# QS40_pcb_1_6_2.net
KiCad netlist of a schematic drawn in EAGLE
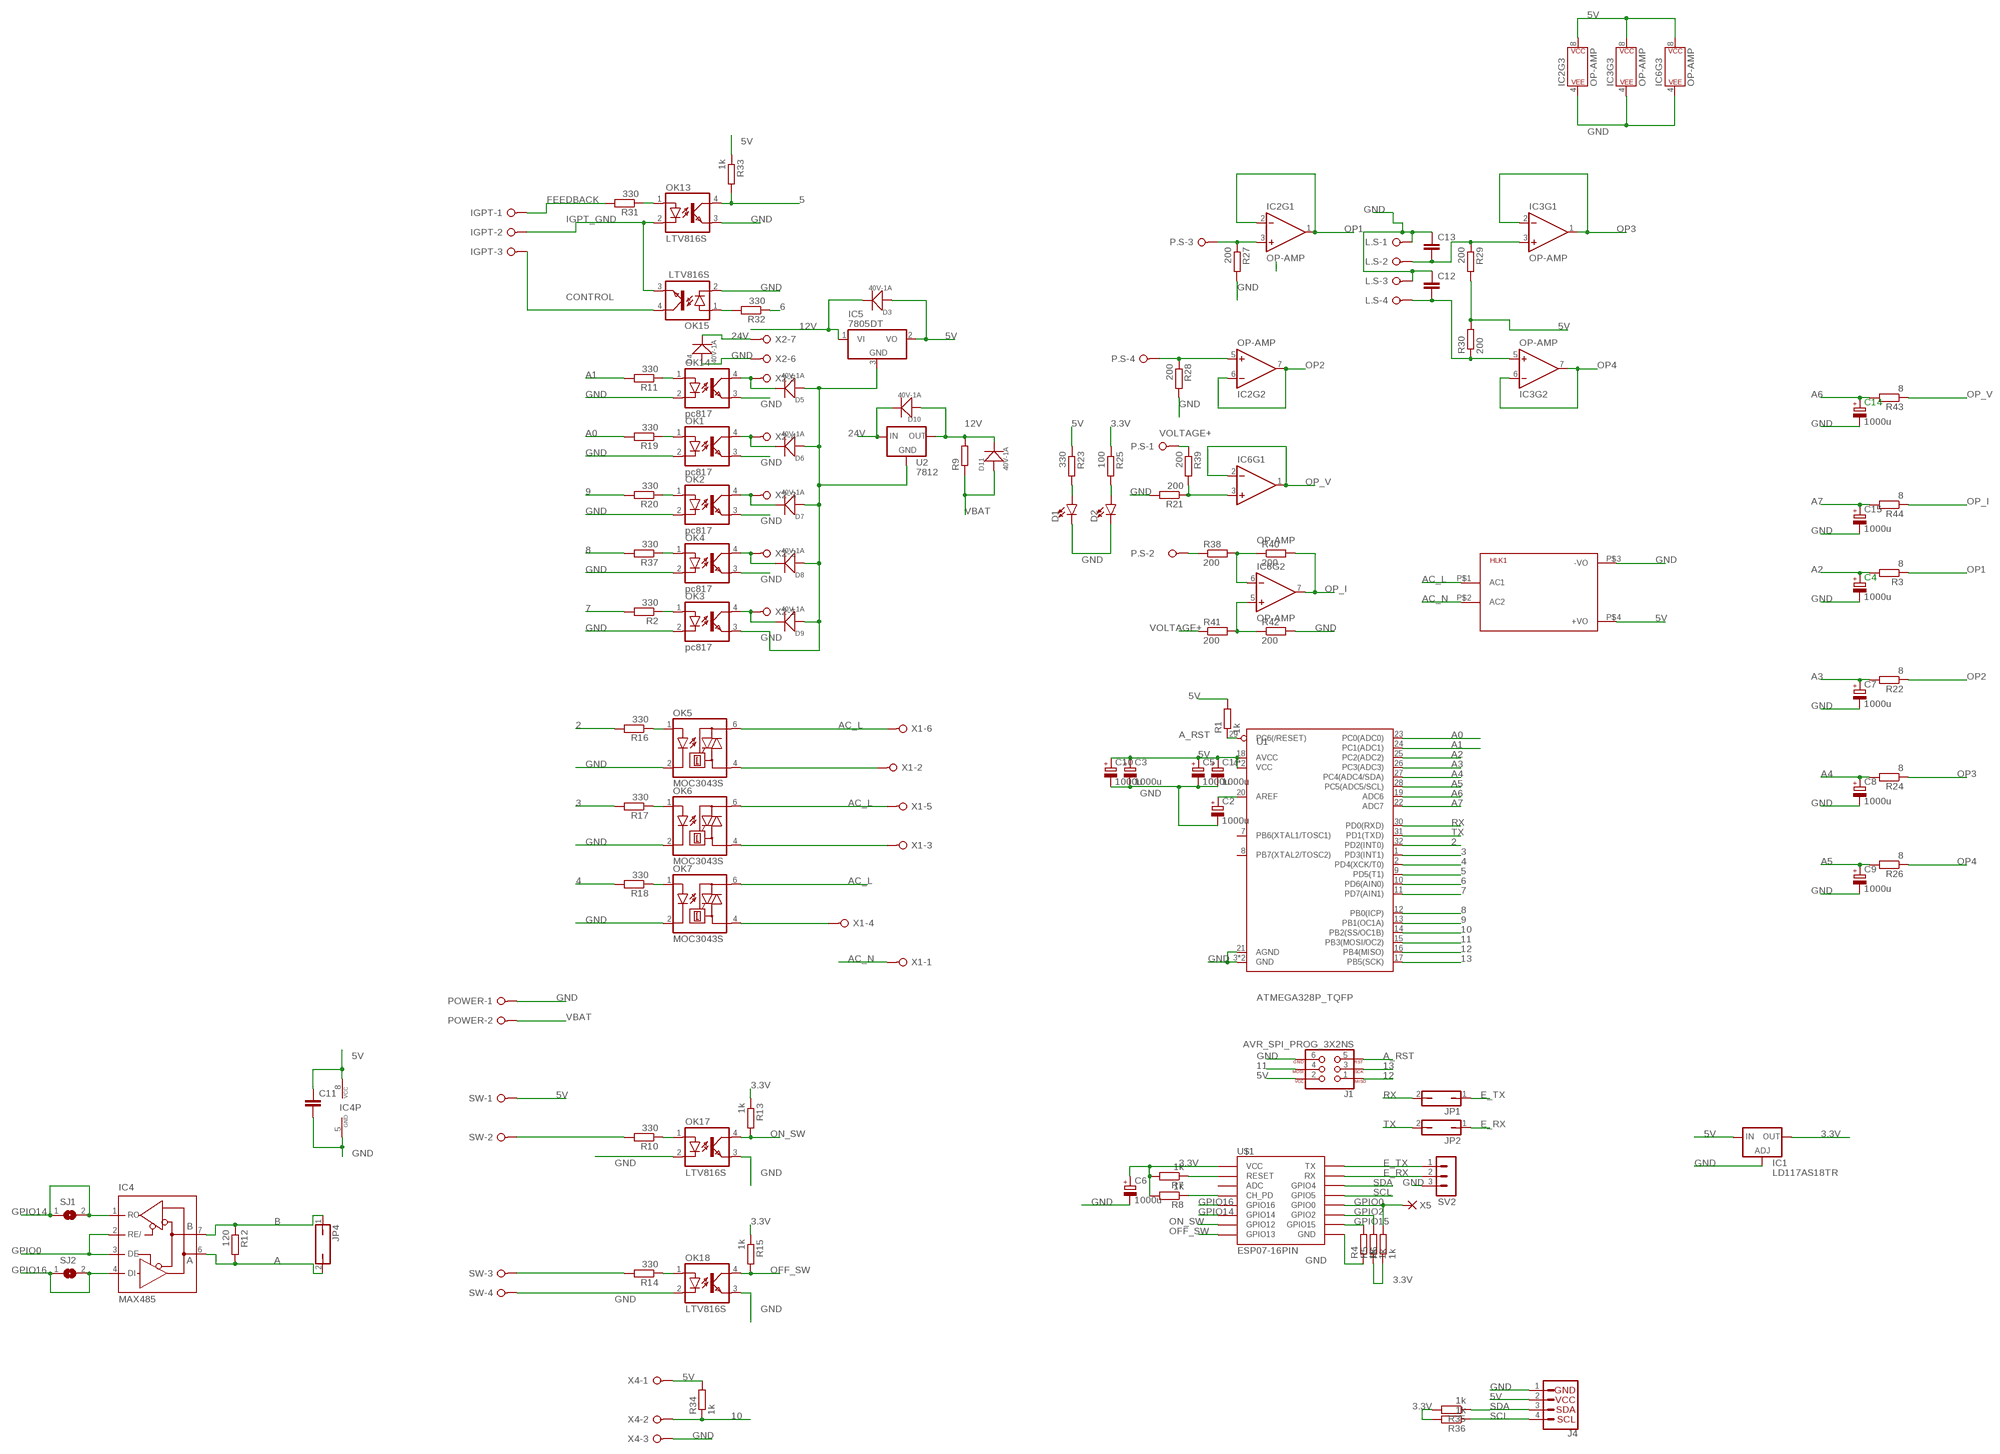
[diagram p0: schematic, sheet 1]

(export (version "E")
  (design (tool "Eeschema 10.0.6"))
  (components
    (comp (ref "C1")
      (value "1000u")
      (footprint "eagle-import:UD-8X10_NICHICON")
      (libsource (lib "eagle-import") (part "CPOL-EUUD-8X10"))
    )
    (comp (ref "C2")
      (value "1000u")
      (footprint "eagle-import:UD-8X10_NICHICON")
      (libsource (lib "eagle-import") (part "CPOL-EUUD-8X10"))
    )
    (comp (ref "C3")
      (value "1000u")
      (footprint "eagle-import:UD-8X10_NICHICON")
      (libsource (lib "eagle-import") (part "CPOL-EUUD-8X10"))
    )
    (comp (ref "C4")
      (value "1000u")
      (footprint "eagle-import:UD-8X10_NICHICON")
      (libsource (lib "eagle-import") (part "CPOL-EUUD-8X10"))
    )
    (comp (ref "C5")
      (value "1000u")
      (footprint "eagle-import:UD-8X10_NICHICON")
      (libsource (lib "eagle-import") (part "CPOL-EUUD-8X10"))
    )
    (comp (ref "C6")
      (value "1000u")
      (footprint "eagle-import:UD-8X10_NICHICON")
      (libsource (lib "eagle-import") (part "CPOL-EUUD-8X10"))
    )
    (comp (ref "C7")
      (value "1000u")
      (footprint "eagle-import:UD-8X10_NICHICON")
      (libsource (lib "eagle-import") (part "CPOL-EUUD-8X10"))
    )
    (comp (ref "C8")
      (value "1000u")
      (footprint "eagle-import:UD-8X10_NICHICON")
      (libsource (lib "eagle-import") (part "CPOL-EUUD-8X10"))
    )
    (comp (ref "C9")
      (value "1000u")
      (footprint "eagle-import:UD-8X10_NICHICON")
      (libsource (lib "eagle-import") (part "CPOL-EUUD-8X10"))
    )
    (comp (ref "C10")
      (value "1000u")
      (footprint "eagle-import:UD-8X10_NICHICON")
      (libsource (lib "eagle-import") (part "CPOL-EUUD-8X10"))
    )
    (comp (ref "C11")
      (value "C-EUC1206K")
      (footprint "eagle-import:C1206K")
      (libsource (lib "eagle-import") (part "C-EUC1206K"))
    )
    (comp (ref "C12")
      (value "C-EUC1206")
      (footprint "eagle-import:C1206")
      (libsource (lib "eagle-import") (part "C-EUC1206"))
    )
    (comp (ref "C13")
      (value "C-EUC1206")
      (footprint "eagle-import:C1206")
      (libsource (lib "eagle-import") (part "C-EUC1206"))
    )
    (comp (ref "C14")
      (value "1000u")
      (footprint "eagle-import:UD-8X10_NICHICON")
      (libsource (lib "eagle-import") (part "CPOL-EUUD-8X10"))
    )
    (comp (ref "C15")
      (value "1000u")
      (footprint "eagle-import:UD-8X10_NICHICON")
      (libsource (lib "eagle-import") (part "CPOL-EUUD-8X10"))
    )
    (comp (ref "D1")
      (value "LED-FKIT-1206")
      (footprint "eagle-import:FKIT-LED-1206")
      (libsource (lib "eagle-import") (part "LED-FKIT-1206"))
    )
    (comp (ref "D2")
      (value "LED-FKIT-1206")
      (footprint "eagle-import:FKIT-LED-1206")
      (libsource (lib "eagle-import") (part "LED-FKIT-1206"))
    )
    (comp (ref "D3")
      (value "40V-1A")
      (footprint "eagle-import:DO-214AC")
      (fields (field (name "MPN") "1N5819"))
      (libsource (lib "eagle-import") (part "SMD-DIODE-SCHOTTKY-40V-1A(DO-214AC)"))
    )
    (comp (ref "D4")
      (value "40V-1A")
      (footprint "eagle-import:DO-214AC")
      (fields (field (name "MPN") "1N5819"))
      (libsource (lib "eagle-import") (part "SMD-DIODE-SCHOTTKY-40V-1A(DO-214AC)"))
    )
    (comp (ref "D5")
      (value "40V-1A")
      (footprint "eagle-import:DO-214AC")
      (fields (field (name "MPN") "1N5819"))
      (libsource (lib "eagle-import") (part "SMD-DIODE-SCHOTTKY-40V-1A(DO-214AC)"))
    )
    (comp (ref "D6")
      (value "40V-1A")
      (footprint "eagle-import:DO-214AC")
      (fields (field (name "MPN") "1N5819"))
      (libsource (lib "eagle-import") (part "SMD-DIODE-SCHOTTKY-40V-1A(DO-214AC)"))
    )
    (comp (ref "D7")
      (value "40V-1A")
      (footprint "eagle-import:DO-214AC")
      (fields (field (name "MPN") "1N5819"))
      (libsource (lib "eagle-import") (part "SMD-DIODE-SCHOTTKY-40V-1A(DO-214AC)"))
    )
    (comp (ref "D8")
      (value "40V-1A")
      (footprint "eagle-import:DO-214AC")
      (fields (field (name "MPN") "1N5819"))
      (libsource (lib "eagle-import") (part "SMD-DIODE-SCHOTTKY-40V-1A(DO-214AC)"))
    )
    (comp (ref "D9")
      (value "40V-1A")
      (footprint "eagle-import:DO-214AC")
      (fields (field (name "MPN") "1N5819"))
      (libsource (lib "eagle-import") (part "SMD-DIODE-SCHOTTKY-40V-1A(DO-214AC)"))
    )
    (comp (ref "D10")
      (value "40V-1A")
      (footprint "eagle-import:DO-214AC")
      (fields (field (name "MPN") "1N5819"))
      (libsource (lib "eagle-import") (part "SMD-DIODE-SCHOTTKY-40V-1A(DO-214AC)"))
    )
    (comp (ref "D11")
      (value "40V-1A")
      (footprint "eagle-import:DO-214AC")
      (fields (field (name "MPN") "1N5819"))
      (libsource (lib "eagle-import") (part "SMD-DIODE-SCHOTTKY-40V-1A(DO-214AC)"))
    )
    (comp (ref "HLK1")
      (value "HLK-PM013W")
      (footprint "eagle-import:HLK-PM01")
      (libsource (lib "eagle-import") (part "HLK-PM013W"))
    )
    (comp (ref "IC1")
      (value "LD117AS18TR")
      (footprint "eagle-import:SOT223")
      (libsource (lib "eagle-import") (part "LD117A?S18TR"))
    )
    (comp (ref "IC2")
      (value "OP-AMP")
      (footprint "eagle-import:SO08")
      (libsource (lib "eagle-import") (part "OPAMP-DUALU"))
    )
    (comp (ref "IC3")
      (value "OP-AMP")
      (footprint "eagle-import:SO08")
      (libsource (lib "eagle-import") (part "OPAMP-DUALU"))
    )
    (comp (ref "IC4")
      (value "MAX485")
      (footprint "eagle-import:SO08")
      (fields (field (name "MF") "MAXIM") (field (name "MPN") "MAX481CSA"))
      (libsource (lib "eagle-import") (part "MAX481CSA"))
    )
    (comp (ref "IC5")
      (value "7805DT")
      (footprint "eagle-import:TO252")
      (libsource (lib "eagle-import") (part "78DT05"))
    )
    (comp (ref "IC6")
      (value "OP-AMP")
      (footprint "eagle-import:SO08")
      (libsource (lib "eagle-import") (part "OPAMP-DUALU"))
    )
    (comp (ref "IGPT")
      (value "W237-03P")
      (footprint "eagle-import:W237-133")
      (libsource (lib "eagle-import") (part "con-wago-508_196_W237-03P"))
    )
    (comp (ref "J1")
      (value "AVR_SPI_PROG_3X2NS")
      (footprint "eagle-import:2X3-NS")
      (libsource (lib "eagle-import") (part "AVR_SPI_PROG_3X2NS"))
    )
    (comp (ref "J4")
      (value "I2C_STANDARD_NO_SILK")
      (footprint "eagle-import:1X04_NO_SILK")
      (libsource (lib "eagle-import") (part "I2C_STANDARD_NO_SILK"))
    )
    (comp (ref "JP1")
      (value "JP1Q")
      (footprint "eagle-import:JP1")
      (libsource (lib "eagle-import") (part "JP1Q"))
    )
    (comp (ref "JP2")
      (value "JP1Q")
      (footprint "eagle-import:JP1")
      (libsource (lib "eagle-import") (part "JP1Q"))
    )
    (comp (ref "JP4")
      (value "JP1Q")
      (footprint "eagle-import:JP1")
      (libsource (lib "eagle-import") (part "JP1Q"))
    )
    (comp (ref "L.S")
      (value "W237-04P")
      (footprint "eagle-import:W237-4P")
      (libsource (lib "eagle-import") (part "W237-04P"))
    )
    (comp (ref "OK1")
      (value "pc817")
      (footprint "eagle-import:DIL4-SMD")
      (libsource (lib "eagle-import") (part "LTV816S"))
    )
    (comp (ref "OK2")
      (value "pc817")
      (footprint "eagle-import:DIL4-SMD")
      (libsource (lib "eagle-import") (part "LTV816S"))
    )
    (comp (ref "OK3")
      (value "pc817")
      (footprint "eagle-import:DIL4-SMD")
      (libsource (lib "eagle-import") (part "LTV816S"))
    )
    (comp (ref "OK4")
      (value "pc817")
      (footprint "eagle-import:DIL4-SMD")
      (libsource (lib "eagle-import") (part "LTV816S"))
    )
    (comp (ref "OK5")
      (value "MOC3043S")
      (footprint "eagle-import:DIL6-SMD")
      (fields (field (name "MF") "FAIRCHILD SEMICONDUCTOR") (field (name "MPN") "MOC3043SM"))
      (libsource (lib "eagle-import") (part "MOC30S43"))
    )
    (comp (ref "OK6")
      (value "MOC3043S")
      (footprint "eagle-import:DIL6-SMD")
      (fields (field (name "MF") "FAIRCHILD SEMICONDUCTOR") (field (name "MPN") "MOC3043SM"))
      (libsource (lib "eagle-import") (part "MOC30S43"))
    )
    (comp (ref "OK7")
      (value "MOC3043S")
      (footprint "eagle-import:DIL6-SMD")
      (fields (field (name "MF") "FAIRCHILD SEMICONDUCTOR") (field (name "MPN") "MOC3043SM"))
      (libsource (lib "eagle-import") (part "MOC30S43"))
    )
    (comp (ref "OK13")
      (value "LTV816S")
      (footprint "eagle-import:DIL4-SMD")
      (libsource (lib "eagle-import") (part "LTV816S"))
    )
    (comp (ref "OK14")
      (value "pc817")
      (footprint "eagle-import:DIL4-SMD")
      (libsource (lib "eagle-import") (part "LTV816S"))
    )
    (comp (ref "OK15")
      (value "LTV816S")
      (footprint "eagle-import:DIL4-SMD")
      (libsource (lib "eagle-import") (part "LTV816S"))
    )
    (comp (ref "OK17")
      (value "LTV816S")
      (footprint "eagle-import:DIL4-SMD")
      (libsource (lib "eagle-import") (part "LTV816S"))
    )
    (comp (ref "OK18")
      (value "LTV816S")
      (footprint "eagle-import:DIL4-SMD")
      (libsource (lib "eagle-import") (part "LTV816S"))
    )
    (comp (ref "P.S")
      (value "W237-04P")
      (footprint "eagle-import:W237-4P")
      (libsource (lib "eagle-import") (part "W237-04P"))
    )
    (comp (ref "POWER")
      (value "W237-02P")
      (footprint "eagle-import:W237-132")
      (libsource (lib "eagle-import") (part "W237-02P"))
    )
    (comp (ref "R1")
      (value "1k")
      (footprint "eagle-import:R1206W")
      (libsource (lib "eagle-import") (part "R-EU_R1206W"))
    )
    (comp (ref "R2")
      (value "330")
      (footprint "eagle-import:R1206W")
      (libsource (lib "eagle-import") (part "R-EU_R1206W"))
    )
    (comp (ref "R3")
      (value "8")
      (footprint "eagle-import:R1206W")
      (libsource (lib "eagle-import") (part "R-EU_R1206W"))
    )
    (comp (ref "R4")
      (value "1k")
      (footprint "eagle-import:R1206W")
      (libsource (lib "eagle-import") (part "R-EU_R1206W"))
    )
    (comp (ref "R5")
      (value "1k")
      (footprint "eagle-import:R1206W")
      (libsource (lib "eagle-import") (part "R-EU_R1206W"))
    )
    (comp (ref "R6")
      (value "1k")
      (footprint "eagle-import:R1206W")
      (libsource (lib "eagle-import") (part "R-EU_R1206W"))
    )
    (comp (ref "R7")
      (value "1k")
      (footprint "eagle-import:R1206W")
      (libsource (lib "eagle-import") (part "R-EU_R1206W"))
    )
    (comp (ref "R8")
      (value "1k")
      (footprint "eagle-import:R1206W")
      (libsource (lib "eagle-import") (part "R-EU_R1206W"))
    )
    (comp (ref "R9")
      (value "R-EU_R5025")
      (footprint "eagle-import:R5025")
      (libsource (lib "eagle-import") (part "R-EU_R5025"))
    )
    (comp (ref "R10")
      (value "330")
      (footprint "eagle-import:R1206W")
      (libsource (lib "eagle-import") (part "R-EU_R1206W"))
    )
    (comp (ref "R11")
      (value "330")
      (footprint "eagle-import:R1206W")
      (libsource (lib "eagle-import") (part "R-EU_R1206W"))
    )
    (comp (ref "R12")
      (value "120")
      (footprint "eagle-import:R1206W")
      (libsource (lib "eagle-import") (part "R-EU_R1206W"))
    )
    (comp (ref "R13")
      (value "1k")
      (footprint "eagle-import:R1206W")
      (libsource (lib "eagle-import") (part "R-EU_R1206W"))
    )
    (comp (ref "R14")
      (value "330")
      (footprint "eagle-import:R1206W")
      (libsource (lib "eagle-import") (part "R-EU_R1206W"))
    )
    (comp (ref "R15")
      (value "1k")
      (footprint "eagle-import:R1206W")
      (libsource (lib "eagle-import") (part "R-EU_R1206W"))
    )
    (comp (ref "R16")
      (value "330")
      (footprint "eagle-import:R1206W")
      (libsource (lib "eagle-import") (part "R-EU_R1206W"))
    )
    (comp (ref "R17")
      (value "330")
      (footprint "eagle-import:R1206W")
      (libsource (lib "eagle-import") (part "R-EU_R1206W"))
    )
    (comp (ref "R18")
      (value "330")
      (footprint "eagle-import:R1206W")
      (libsource (lib "eagle-import") (part "R-EU_R1206W"))
    )
    (comp (ref "R19")
      (value "330")
      (footprint "eagle-import:R1206W")
      (libsource (lib "eagle-import") (part "R-EU_R1206W"))
    )
    (comp (ref "R20")
      (value "330")
      (footprint "eagle-import:R1206W")
      (libsource (lib "eagle-import") (part "R-EU_R1206W"))
    )
    (comp (ref "R21")
      (value "200")
      (footprint "eagle-import:R1206")
      (libsource (lib "eagle-import") (part "R-EU_R1206"))
    )
    (comp (ref "R22")
      (value "8")
      (footprint "eagle-import:R1206W")
      (libsource (lib "eagle-import") (part "R-EU_R1206W"))
    )
    (comp (ref "R23")
      (value "330")
      (footprint "eagle-import:R1206W")
      (libsource (lib "eagle-import") (part "R-EU_R1206W"))
    )
    (comp (ref "R24")
      (value "8")
      (footprint "eagle-import:R1206W")
      (libsource (lib "eagle-import") (part "R-EU_R1206W"))
    )
    (comp (ref "R25")
      (value "100")
      (footprint "eagle-import:R1206W")
      (libsource (lib "eagle-import") (part "R-EU_R1206W"))
    )
    (comp (ref "R26")
      (value "8")
      (footprint "eagle-import:R1206W")
      (libsource (lib "eagle-import") (part "R-EU_R1206W"))
    )
    (comp (ref "R27")
      (value "200")
      (footprint "eagle-import:R1206")
      (libsource (lib "eagle-import") (part "R-EU_R1206"))
    )
    (comp (ref "R28")
      (value "200")
      (footprint "eagle-import:R1206")
      (libsource (lib "eagle-import") (part "R-EU_R1206"))
    )
    (comp (ref "R29")
      (value "200")
      (footprint "eagle-import:R1206W")
      (libsource (lib "eagle-import") (part "R-EU_R1206W"))
    )
    (comp (ref "R30")
      (value "200")
      (footprint "eagle-import:R1206W")
      (libsource (lib "eagle-import") (part "R-EU_R1206W"))
    )
    (comp (ref "R31")
      (value "330")
      (footprint "eagle-import:R1206W")
      (libsource (lib "eagle-import") (part "R-EU_R1206W"))
    )
    (comp (ref "R32")
      (value "330")
      (footprint "eagle-import:R1206W")
      (libsource (lib "eagle-import") (part "R-EU_R1206W"))
    )
    (comp (ref "R33")
      (value "1k")
      (footprint "eagle-import:R1206W")
      (libsource (lib "eagle-import") (part "R-EU_R1206W"))
    )
    (comp (ref "R34")
      (value "1k")
      (footprint "eagle-import:R1206W")
      (libsource (lib "eagle-import") (part "R-EU_R1206W"))
    )
    (comp (ref "R35")
      (value "1k")
      (footprint "eagle-import:R1206W")
      (libsource (lib "eagle-import") (part "R-EU_R1206W"))
    )
    (comp (ref "R36")
      (value "1k")
      (footprint "eagle-import:R1206W")
      (libsource (lib "eagle-import") (part "R-EU_R1206W"))
    )
    (comp (ref "R37")
      (value "330")
      (footprint "eagle-import:R1206W")
      (libsource (lib "eagle-import") (part "R-EU_R1206W"))
    )
    (comp (ref "R38")
      (value "200")
      (footprint "eagle-import:R1206")
      (libsource (lib "eagle-import") (part "R-EU_R1206"))
    )
    (comp (ref "R39")
      (value "200")
      (footprint "eagle-import:R1206")
      (libsource (lib "eagle-import") (part "R-EU_R1206"))
    )
    (comp (ref "R40")
      (value "200")
      (footprint "eagle-import:R1206")
      (libsource (lib "eagle-import") (part "R-EU_R1206"))
    )
    (comp (ref "R41")
      (value "200")
      (footprint "eagle-import:R1206")
      (libsource (lib "eagle-import") (part "R-EU_R1206"))
    )
    (comp (ref "R42")
      (value "200")
      (footprint "eagle-import:R1206")
      (libsource (lib "eagle-import") (part "R-EU_R1206"))
    )
    (comp (ref "R43")
      (value "8")
      (footprint "eagle-import:R1206W")
      (libsource (lib "eagle-import") (part "R-EU_R1206W"))
    )
    (comp (ref "R44")
      (value "8")
      (footprint "eagle-import:R1206W")
      (libsource (lib "eagle-import") (part "R-EU_R1206W"))
    )
    (comp (ref "SJ1") (value "SJ") (footprint "eagle-import:SJ") (libsource (lib "eagle-import") (part "SJ")))
    (comp (ref "SJ2") (value "SJ") (footprint "eagle-import:SJ") (libsource (lib "eagle-import") (part "SJ")))
    (comp (ref "SV2")
      (value "MA03-1")
      (footprint "eagle-import:MA03-1")
      (libsource (lib "eagle-import") (part "MA03-1"))
    )
    (comp (ref "SW")
      (value "W237-04P")
      (footprint "eagle-import:W237-4P")
      (libsource (lib "eagle-import") (part "W237-04P"))
    )
    (comp (ref "U$1")
      (value "ESP07-16PIN")
      (footprint "eagle-import:ESP07")
      (libsource (lib "eagle-import") (part "ESP07-16PIN"))
    )
    (comp (ref "U1")
      (value "ATMEGA328P_TQFP")
      (footprint "eagle-import:TQFP32-08")
      (libsource (lib "eagle-import") (part "ATMEGA328P_TQFP"))
    )
    (comp (ref "U2")
      (value "7812")
      (footprint "eagle-import:TO-252")
      (libsource (lib "eagle-import") (part "V_REG_78XX7812"))
    )
    (comp (ref "X1")
      (value "W237-06P")
      (footprint "eagle-import:W237-6P")
      (libsource (lib "eagle-import") (part "W237-06P"))
    )
    (comp (ref "X2")
      (value "W237-07P")
      (footprint "eagle-import:W237-7P")
      (libsource (lib "eagle-import") (part "W237-07P"))
    )
    (comp (ref "X4")
      (value "W237-03P")
      (footprint "eagle-import:W237-133")
      (libsource (lib "eagle-import") (part "W237-03P"))
    )
    (comp (ref "X5")
      (value "PAD-1.00-2.00")
      (footprint "eagle-import:PAD-1.00-2.00")
      (libsource (lib "eagle-import") (part "PAD-1.00-2.00"))
    )
  )
  (nets
    (net (code "1") (name "/2") (class "Default")
      (node (ref "R16") (pin "2") (pinfunction "2_2") (pintype "passive"))
      (node (ref "U1") (pin "32") (pinfunction "PD2(INT0)_32") (pintype "bidirectional"))
    )
    (net (code "2") (name "/3") (class "Default")
      (node (ref "R17") (pin "2") (pinfunction "2_2") (pintype "passive"))
      (node (ref "U1") (pin "1") (pinfunction "PD3(INT1)_1") (pintype "bidirectional"))
    )
    (net (code "3") (name "/3.3V") (class "Default")
      (node (ref "C6") (pin "+") (pinfunction "+_+") (pintype "passive"))
      (node (ref "IC1") (pin "4") (pinfunction "OUT_4") (pintype "passive"))
      (node (ref "R13") (pin "1") (pinfunction "1_1") (pintype "passive"))
      (node (ref "R15") (pin "1") (pinfunction "1_1") (pintype "passive"))
      (node (ref "R25") (pin "1") (pinfunction "1_1") (pintype "passive"))
      (node (ref "R35") (pin "2") (pinfunction "2_2") (pintype "passive"))
      (node (ref "R36") (pin "2") (pinfunction "2_2") (pintype "passive"))
      (node (ref "R5") (pin "1") (pinfunction "1_1") (pintype "passive"))
      (node (ref "R6") (pin "1") (pinfunction "1_1") (pintype "passive"))
      (node (ref "R7") (pin "2") (pinfunction "2_2") (pintype "passive"))
      (node (ref "R8") (pin "2") (pinfunction "2_2") (pintype "passive"))
      (node (ref "U$1") (pin "VCC") (pinfunction "VCC_VCC") (pintype "bidirectional"))
    )
    (net (code "4") (name "/4") (class "Default")
      (node (ref "R18") (pin "2") (pinfunction "2_2") (pintype "passive"))
      (node (ref "U1") (pin "2") (pinfunction "PD4(XCK/T0)_2") (pintype "bidirectional"))
    )
    (net (code "5") (name "/5") (class "Default")
      (node (ref "OK13") (pin "4") (pinfunction "COL_4") (pintype "passive"))
      (node (ref "R33") (pin "2") (pinfunction "2_2") (pintype "passive"))
      (node (ref "U1") (pin "9") (pinfunction "PD5(T1)_9") (pintype "bidirectional"))
    )
    (net (code "6") (name "/5V") (class "Default")
      (node (ref "C1") (pin "+") (pinfunction "+_+") (pintype "passive"))
      (node (ref "C10") (pin "+") (pinfunction "+_+") (pintype "passive"))
      (node (ref "C11") (pin "1") (pinfunction "1_1") (pintype "passive"))
      (node (ref "C3") (pin "+") (pinfunction "+_+") (pintype "passive"))
      (node (ref "C5") (pin "+") (pinfunction "+_+") (pintype "passive"))
      (node (ref "D3") (pin "1") (pinfunction "+_1") (pintype "passive"))
      (node (ref "HLK1") (pin "P$4") (pinfunction "+VO_P$4") (pintype "bidirectional"))
      (node (ref "IC1") (pin "3") (pinfunction "IN_3") (pintype "input"))
      (node (ref "IC2") (pin "8") (pinfunction "P$V+_8") (pintype "bidirectional"))
      (node (ref "IC3") (pin "8") (pinfunction "P$V+_8") (pintype "bidirectional"))
      (node (ref "IC4") (pin "8") (pinfunction "VCC_8") (pintype "power_in"))
      (node (ref "IC5") (pin "2") (pinfunction "VO_2") (pintype "passive"))
      (node (ref "IC6") (pin "8") (pinfunction "P$V+_8") (pintype "bidirectional"))
      (node (ref "J1") (pin "2") (pinfunction "2_2") (pintype "passive"))
      (node (ref "J4") (pin "2") (pinfunction "2_2") (pintype "power_in"))
      (node (ref "R1") (pin "2") (pinfunction "2_2") (pintype "passive"))
      (node (ref "R23") (pin "1") (pinfunction "1_1") (pintype "passive"))
      (node (ref "R29") (pin "2") (pinfunction "2_2") (pintype "passive"))
      (node (ref "R30") (pin "2") (pinfunction "2_2") (pintype "passive"))
      (node (ref "R33") (pin "1") (pinfunction "1_1") (pintype "passive"))
      (node (ref "R34") (pin "2") (pinfunction "2_2") (pintype "passive"))
      (node (ref "SW") (pin "1") (pinfunction "KL_1") (pintype "passive"))
      (node (ref "U1") (pin "18") (pinfunction "AVCC_18") (pintype "bidirectional"))
      (node (ref "U1") (pin "4") (pinfunction "VCC_4") (pintype "bidirectional"))
      (node (ref "U1") (pin "6") (pinfunction "VCC_6") (pintype "bidirectional"))
      (node (ref "X4") (pin "1") (pinfunction "KL_1") (pintype "passive"))
    )
    (net (code "7") (name "/6") (class "Default")
      (node (ref "R32") (pin "1") (pinfunction "1_1") (pintype "passive"))
      (node (ref "U1") (pin "10") (pinfunction "PD6(AIN0)_10") (pintype "bidirectional"))
    )
    (net (code "8") (name "/7") (class "Default")
      (node (ref "R2") (pin "2") (pinfunction "2_2") (pintype "passive"))
      (node (ref "U1") (pin "11") (pinfunction "PD7(AIN1)_11") (pintype "bidirectional"))
    )
    (net (code "9") (name "/8") (class "Default")
      (node (ref "R37") (pin "2") (pinfunction "2_2") (pintype "passive"))
      (node (ref "U1") (pin "12") (pinfunction "PB0(ICP)_12") (pintype "bidirectional"))
    )
    (net (code "10") (name "/9") (class "Default")
      (node (ref "R20") (pin "2") (pinfunction "2_2") (pintype "passive"))
      (node (ref "U1") (pin "13") (pinfunction "PB1(OC1A)_13") (pintype "bidirectional"))
    )
    (net (code "11") (name "/10") (class "Default")
      (node (ref "R34") (pin "1") (pinfunction "1_1") (pintype "passive"))
      (node (ref "U1") (pin "14") (pinfunction "PB2(SS/OC1B)_14") (pintype "bidirectional"))
      (node (ref "X4") (pin "2") (pinfunction "KL_2") (pintype "passive"))
    )
    (net (code "12") (name "/11") (class "Default")
      (node (ref "J1") (pin "4") (pinfunction "4_4") (pintype "passive"))
      (node (ref "U1") (pin "15") (pinfunction "PB3(MOSI/OC2)_15") (pintype "bidirectional"))
    )
    (net (code "13") (name "/12") (class "Default")
      (node (ref "J1") (pin "1") (pinfunction "1_1") (pintype "passive"))
      (node (ref "U1") (pin "16") (pinfunction "PB4(MISO)_16") (pintype "bidirectional"))
    )
    (net (code "14") (name "/12V") (class "Default")
      (node (ref "D10") (pin "1") (pinfunction "+_1") (pintype "passive"))
      (node (ref "D11") (pin "2") (pinfunction "-_2") (pintype "passive"))
      (node (ref "D3") (pin "2") (pinfunction "-_2") (pintype "passive"))
      (node (ref "IC5") (pin "1") (pinfunction "VI_1") (pintype "input"))
      (node (ref "R9") (pin "2") (pinfunction "2_2") (pintype "passive"))
      (node (ref "U2") (pin "2") (pinfunction "OUT_2") (pintype "passive"))
    )
    (net (code "15") (name "/13") (class "Default")
      (node (ref "J1") (pin "3") (pinfunction "3_3") (pintype "passive"))
      (node (ref "U1") (pin "17") (pinfunction "PB5(SCK)_17") (pintype "bidirectional"))
    )
    (net (code "16") (name "/24V") (class "Default")
      (node (ref "D10") (pin "2") (pinfunction "-_2") (pintype "passive"))
      (node (ref "D4") (pin "2") (pinfunction "-_2") (pintype "passive"))
      (node (ref "U2") (pin "1") (pinfunction "IN_1") (pintype "input"))
      (node (ref "X2") (pin "7") (pinfunction "KL_7") (pintype "passive"))
    )
    (net (code "17") (name "/A") (class "Default")
      (node (ref "IC4") (pin "6") (pinfunction "A_6") (pintype "passive"))
      (node (ref "JP4") (pin "2") (pinfunction "2_2") (pintype "passive"))
      (node (ref "R12") (pin "2") (pinfunction "2_2") (pintype "passive"))
    )
    (net (code "18") (name "/A0") (class "Default")
      (node (ref "R19") (pin "2") (pinfunction "2_2") (pintype "passive"))
      (node (ref "U1") (pin "23") (pinfunction "PC0(ADC0)_23") (pintype "bidirectional"))
    )
    (net (code "19") (name "/A1") (class "Default")
      (node (ref "R11") (pin "2") (pinfunction "2_2") (pintype "passive"))
      (node (ref "U1") (pin "24") (pinfunction "PC1(ADC1)_24") (pintype "bidirectional"))
    )
    (net (code "20") (name "/A2") (class "Default")
      (node (ref "C4") (pin "+") (pinfunction "+_+") (pintype "passive"))
      (node (ref "R3") (pin "2") (pinfunction "2_2") (pintype "passive"))
      (node (ref "U1") (pin "25") (pinfunction "PC2(ADC2)_25") (pintype "bidirectional"))
    )
    (net (code "21") (name "/A3") (class "Default")
      (node (ref "C7") (pin "+") (pinfunction "+_+") (pintype "passive"))
      (node (ref "R22") (pin "2") (pinfunction "2_2") (pintype "passive"))
      (node (ref "U1") (pin "26") (pinfunction "PC3(ADC3)_26") (pintype "bidirectional"))
    )
    (net (code "22") (name "/A4") (class "Default")
      (node (ref "C8") (pin "+") (pinfunction "+_+") (pintype "passive"))
      (node (ref "R24") (pin "2") (pinfunction "2_2") (pintype "passive"))
      (node (ref "U1") (pin "27") (pinfunction "PC4(ADC4/SDA)_27") (pintype "bidirectional"))
    )
    (net (code "23") (name "/A5") (class "Default")
      (node (ref "C9") (pin "+") (pinfunction "+_+") (pintype "passive"))
      (node (ref "R26") (pin "2") (pinfunction "2_2") (pintype "passive"))
      (node (ref "U1") (pin "28") (pinfunction "PC5(ADC5/SCL)_28") (pintype "bidirectional"))
    )
    (net (code "24") (name "/A6") (class "Default")
      (node (ref "C14") (pin "+") (pinfunction "+_+") (pintype "passive"))
      (node (ref "R43") (pin "2") (pinfunction "2_2") (pintype "passive"))
      (node (ref "U1") (pin "19") (pinfunction "ADC6_19") (pintype "bidirectional"))
    )
    (net (code "25") (name "/A7") (class "Default")
      (node (ref "C15") (pin "+") (pinfunction "+_+") (pintype "passive"))
      (node (ref "R44") (pin "2") (pinfunction "2_2") (pintype "passive"))
      (node (ref "U1") (pin "22") (pinfunction "ADC7_22") (pintype "bidirectional"))
    )
    (net (code "26") (name "/AC_L") (class "Default")
      (node (ref "HLK1") (pin "P$1") (pinfunction "AC1_P$1") (pintype "bidirectional"))
      (node (ref "OK5") (pin "6") (pinfunction "A2_6") (pintype "passive"))
      (node (ref "OK6") (pin "6") (pinfunction "A2_6") (pintype "passive"))
      (node (ref "OK7") (pin "6") (pinfunction "A2_6") (pintype "passive"))
      (node (ref "X1") (pin "5") (pinfunction "KL_5") (pintype "passive"))
      (node (ref "X1") (pin "6") (pinfunction "KL_6") (pintype "passive"))
    )
    (net (code "27") (name "/AC_N") (class "Default")
      (node (ref "HLK1") (pin "P$2") (pinfunction "AC2_P$2") (pintype "bidirectional"))
      (node (ref "X1") (pin "1") (pinfunction "KL_1") (pintype "passive"))
    )
    (net (code "28") (name "/A_RST") (class "Default")
      (node (ref "J1") (pin "5") (pinfunction "5_5") (pintype "passive"))
      (node (ref "R1") (pin "1") (pinfunction "1_1") (pintype "passive"))
      (node (ref "U1") (pin "29") (pinfunction "PC6(/RESET)_29") (pintype "bidirectional"))
    )
    (net (code "29") (name "/B") (class "Default")
      (node (ref "IC4") (pin "7") (pinfunction "B_7") (pintype "passive"))
      (node (ref "JP4") (pin "1") (pinfunction "1_1") (pintype "passive"))
      (node (ref "R12") (pin "1") (pinfunction "1_1") (pintype "passive"))
    )
    (net (code "30") (name "/CONTROL") (class "Default")
      (node (ref "IGPT") (pin "3") (pinfunction "KL_3") (pintype "passive"))
      (node (ref "OK15") (pin "4") (pinfunction "COL_4") (pintype "passive"))
    )
    (net (code "31") (name "/E_RX") (class "Default")
      (node (ref "JP2") (pin "1") (pinfunction "1_1") (pintype "passive"))
      (node (ref "SV2") (pin "2") (pinfunction "2_2") (pintype "passive"))
      (node (ref "U$1") (pin "RX") (pinfunction "RX_RX") (pintype "bidirectional"))
    )
    (net (code "32") (name "/E_TX") (class "Default")
      (node (ref "JP1") (pin "1") (pinfunction "1_1") (pintype "passive"))
      (node (ref "SV2") (pin "1") (pinfunction "1_1") (pintype "passive"))
      (node (ref "U$1") (pin "TX") (pinfunction "TX_TX") (pintype "bidirectional"))
    )
    (net (code "33") (name "/FEEDBACK") (class "Default")
      (node (ref "IGPT") (pin "1") (pinfunction "KL_1") (pintype "passive"))
      (node (ref "R31") (pin "2") (pinfunction "2_2") (pintype "passive"))
    )
    (net (code "34") (name "/GND") (class "Default")
      (node (ref "C1") (pin "-") (pinfunction "-_-") (pintype "passive"))
      (node (ref "C10") (pin "-") (pinfunction "-_-") (pintype "passive"))
      (node (ref "C11") (pin "2") (pinfunction "2_2") (pintype "passive"))
      (node (ref "C12") (pin "1") (pinfunction "1_1") (pintype "passive"))
      (node (ref "C13") (pin "1") (pinfunction "1_1") (pintype "passive"))
      (node (ref "C14") (pin "-") (pinfunction "-_-") (pintype "passive"))
      (node (ref "C15") (pin "-") (pinfunction "-_-") (pintype "passive"))
      (node (ref "C2") (pin "-") (pinfunction "-_-") (pintype "passive"))
      (node (ref "C3") (pin "-") (pinfunction "-_-") (pintype "passive"))
      (node (ref "C4") (pin "-") (pinfunction "-_-") (pintype "passive"))
      (node (ref "C5") (pin "-") (pinfunction "-_-") (pintype "passive"))
      (node (ref "C6") (pin "-") (pinfunction "-_-") (pintype "passive"))
      (node (ref "C7") (pin "-") (pinfunction "-_-") (pintype "passive"))
      (node (ref "C8") (pin "-") (pinfunction "-_-") (pintype "passive"))
      (node (ref "C9") (pin "-") (pinfunction "-_-") (pintype "passive"))
      (node (ref "D1") (pin "C") (pinfunction "C_C") (pintype "passive"))
      (node (ref "D2") (pin "C") (pinfunction "C_C") (pintype "passive"))
      (node (ref "D4") (pin "1") (pinfunction "+_1") (pintype "passive"))
      (node (ref "D5") (pin "1") (pinfunction "+_1") (pintype "passive"))
      (node (ref "D6") (pin "1") (pinfunction "+_1") (pintype "passive"))
      (node (ref "D7") (pin "1") (pinfunction "+_1") (pintype "passive"))
      (node (ref "D8") (pin "1") (pinfunction "+_1") (pintype "passive"))
      (node (ref "D9") (pin "1") (pinfunction "+_1") (pintype "passive"))
      (node (ref "HLK1") (pin "P$3") (pinfunction "-VO_P$3") (pintype "bidirectional"))
      (node (ref "IC1") (pin "1") (pinfunction "ADJ_1") (pintype "input"))
      (node (ref "IC2") (pin "4") (pinfunction "P$V-_4") (pintype "bidirectional"))
      (node (ref "IC3") (pin "4") (pinfunction "P$V-_4") (pintype "bidirectional"))
      (node (ref "IC4") (pin "5") (pinfunction "GND_5") (pintype "power_in"))
      (node (ref "IC5") (pin "3") (pinfunction "GND_3") (pintype "passive"))
      (node (ref "IC6") (pin "4") (pinfunction "P$V-_4") (pintype "bidirectional"))
      (node (ref "J1") (pin "6") (pinfunction "6_6") (pintype "passive"))
      (node (ref "J4") (pin "1") (pinfunction "1_1") (pintype "power_in"))
      (node (ref "L.S") (pin "1") (pinfunction "KL_1") (pintype "passive"))
      (node (ref "L.S") (pin "3") (pinfunction "KL_3") (pintype "passive"))
      (node (ref "OK1") (pin "2") (pinfunction "C_2") (pintype "passive"))
      (node (ref "OK1") (pin "3") (pinfunction "EMIT_3") (pintype "passive"))
      (node (ref "OK13") (pin "3") (pinfunction "EMIT_3") (pintype "passive"))
      (node (ref "OK14") (pin "2") (pinfunction "C_2") (pintype "passive"))
      (node (ref "OK14") (pin "3") (pinfunction "EMIT_3") (pintype "passive"))
      (node (ref "OK15") (pin "2") (pinfunction "C_2") (pintype "passive"))
      (node (ref "OK17") (pin "2") (pinfunction "C_2") (pintype "passive"))
      (node (ref "OK17") (pin "3") (pinfunction "EMIT_3") (pintype "passive"))
      (node (ref "OK18") (pin "2") (pinfunction "C_2") (pintype "passive"))
      (node (ref "OK18") (pin "3") (pinfunction "EMIT_3") (pintype "passive"))
      (node (ref "OK2") (pin "2") (pinfunction "C_2") (pintype "passive"))
      (node (ref "OK2") (pin "3") (pinfunction "EMIT_3") (pintype "passive"))
      (node (ref "OK3") (pin "2") (pinfunction "C_2") (pintype "passive"))
      (node (ref "OK3") (pin "3") (pinfunction "EMIT_3") (pintype "passive"))
      (node (ref "OK4") (pin "2") (pinfunction "C_2") (pintype "passive"))
      (node (ref "OK4") (pin "3") (pinfunction "EMIT_3") (pintype "passive"))
      (node (ref "OK5") (pin "2") (pinfunction "C_2") (pintype "passive"))
      (node (ref "OK6") (pin "2") (pinfunction "C_2") (pintype "passive"))
      (node (ref "OK7") (pin "2") (pinfunction "C_2") (pintype "passive"))
      (node (ref "POWER") (pin "1") (pinfunction "KL_1") (pintype "passive"))
      (node (ref "R21") (pin "2") (pinfunction "2_2") (pintype "passive"))
      (node (ref "R27") (pin "2") (pinfunction "2_2") (pintype "passive"))
      (node (ref "R28") (pin "2") (pinfunction "2_2") (pintype "passive"))
      (node (ref "R4") (pin "1") (pinfunction "1_1") (pintype "passive"))
      (node (ref "R42") (pin "2") (pinfunction "2_2") (pintype "passive"))
      (node (ref "SV2") (pin "3") (pinfunction "3_3") (pintype "passive"))
      (node (ref "SW") (pin "4") (pinfunction "KL_4") (pintype "passive"))
      (node (ref "U$1") (pin "GND") (pinfunction "GND_GND") (pintype "bidirectional"))
      (node (ref "U1") (pin "21") (pinfunction "AGND_21") (pintype "bidirectional"))
      (node (ref "U1") (pin "3") (pinfunction "GND_3") (pintype "bidirectional"))
      (node (ref "U1") (pin "5") (pinfunction "GND_5") (pintype "bidirectional"))
      (node (ref "U2") (pin "3") (pinfunction "GND_3") (pintype "input"))
      (node (ref "X2") (pin "6") (pinfunction "KL_6") (pintype "passive"))
      (node (ref "X4") (pin "3") (pinfunction "KL_3") (pintype "passive"))
    )
    (net (code "35") (name "/GPIO0") (class "Default")
      (node (ref "IC4") (pin "2") (pinfunction "RE/_2") (pintype "input"))
      (node (ref "IC4") (pin "3") (pinfunction "DE_3") (pintype "input"))
      (node (ref "R6") (pin "2") (pinfunction "2_2") (pintype "passive"))
      (node (ref "U$1") (pin "GPIO0") (pinfunction "GPIO0_GPIO0") (pintype "bidirectional"))
      (node (ref "X5") (pin "1") (pinfunction "P_1") (pintype "passive"))
    )
    (net (code "36") (name "/GPIO2") (class "Default")
      (node (ref "R5") (pin "2") (pinfunction "2_2") (pintype "passive"))
      (node (ref "U$1") (pin "GPIO2") (pinfunction "GPIO2_GPIO2") (pintype "bidirectional"))
    )
    (net (code "37") (name "/GPIO14") (class "Default")
      (node (ref "IC4") (pin "1") (pinfunction "RO_1") (pintype "output"))
      (node (ref "SJ1") (pin "1") (pinfunction "1_1") (pintype "passive"))
      (node (ref "SJ1") (pin "2") (pinfunction "2_2") (pintype "passive"))
      (node (ref "U$1") (pin "GPIO14") (pinfunction "GPIO14_GPIO14") (pintype "bidirectional"))
    )
    (net (code "38") (name "/GPIO15") (class "Default")
      (node (ref "R4") (pin "2") (pinfunction "2_2") (pintype "passive"))
      (node (ref "U$1") (pin "GPIO15") (pinfunction "GPIO15_GPIO15") (pintype "bidirectional"))
    )
    (net (code "39") (name "/GPIO16") (class "Default")
      (node (ref "IC4") (pin "4") (pinfunction "DI_4") (pintype "input"))
      (node (ref "SJ2") (pin "1") (pinfunction "1_1") (pintype "passive"))
      (node (ref "SJ2") (pin "2") (pinfunction "2_2") (pintype "passive"))
      (node (ref "U$1") (pin "GPIO16") (pinfunction "GPIO16_GPIO16") (pintype "bidirectional"))
    )
    (net (code "40") (name "/IGPT_GND") (class "Default")
      (node (ref "IGPT") (pin "2") (pinfunction "KL_2") (pintype "passive"))
      (node (ref "OK13") (pin "2") (pinfunction "C_2") (pintype "passive"))
      (node (ref "OK15") (pin "3") (pinfunction "EMIT_3") (pintype "passive"))
    )
    (net (code "41") (name "/OFF_SW") (class "Default")
      (node (ref "OK18") (pin "4") (pinfunction "COL_4") (pintype "passive"))
      (node (ref "R15") (pin "2") (pinfunction "2_2") (pintype "passive"))
      (node (ref "U$1") (pin "GPIO13") (pinfunction "GPIO13_GPIO13") (pintype "bidirectional"))
    )
    (net (code "42") (name "/ON_SW") (class "Default")
      (node (ref "OK17") (pin "4") (pinfunction "COL_4") (pintype "passive"))
      (node (ref "R13") (pin "2") (pinfunction "2_2") (pintype "passive"))
      (node (ref "U$1") (pin "GPIO12") (pinfunction "GPIO12_GPIO12") (pintype "bidirectional"))
    )
    (net (code "43") (name "/OP1") (class "Default")
      (node (ref "IC2") (pin "1") (pinfunction "OUT_1") (pintype "output"))
      (node (ref "IC2") (pin "2") (pinfunction "-IN_2") (pintype "input"))
      (node (ref "R3") (pin "1") (pinfunction "1_1") (pintype "passive"))
    )
    (net (code "44") (name "/OP2") (class "Default")
      (node (ref "IC2") (pin "6") (pinfunction "-IN_6") (pintype "input"))
      (node (ref "IC2") (pin "7") (pinfunction "OUT_7") (pintype "output"))
      (node (ref "R22") (pin "1") (pinfunction "1_1") (pintype "passive"))
    )
    (net (code "45") (name "/OP3") (class "Default")
      (node (ref "IC3") (pin "1") (pinfunction "OUT_1") (pintype "output"))
      (node (ref "IC3") (pin "2") (pinfunction "-IN_2") (pintype "input"))
      (node (ref "R24") (pin "1") (pinfunction "1_1") (pintype "passive"))
    )
    (net (code "46") (name "/OP4") (class "Default")
      (node (ref "IC3") (pin "6") (pinfunction "-IN_6") (pintype "input"))
      (node (ref "IC3") (pin "7") (pinfunction "OUT_7") (pintype "output"))
      (node (ref "R26") (pin "1") (pinfunction "1_1") (pintype "passive"))
    )
    (net (code "47") (name "/OP_I") (class "Default")
      (node (ref "IC6") (pin "7") (pinfunction "OUT_7") (pintype "output"))
      (node (ref "R40") (pin "2") (pinfunction "2_2") (pintype "passive"))
      (node (ref "R44") (pin "1") (pinfunction "1_1") (pintype "passive"))
    )
    (net (code "48") (name "/OP_V") (class "Default")
      (node (ref "IC6") (pin "1") (pinfunction "OUT_1") (pintype "output"))
      (node (ref "IC6") (pin "2") (pinfunction "-IN_2") (pintype "input"))
      (node (ref "R43") (pin "1") (pinfunction "1_1") (pintype "passive"))
    )
    (net (code "49") (name "/RX") (class "Default")
      (node (ref "JP1") (pin "2") (pinfunction "2_2") (pintype "passive"))
      (node (ref "U1") (pin "30") (pinfunction "PD0(RXD)_30") (pintype "bidirectional"))
    )
    (net (code "50") (name "/SCL") (class "Default")
      (node (ref "J4") (pin "4") (pinfunction "4_4") (pintype "passive"))
      (node (ref "R36") (pin "1") (pinfunction "1_1") (pintype "passive"))
      (node (ref "U$1") (pin "GPIO5") (pinfunction "GPIO5_GPIO5") (pintype "bidirectional"))
    )
    (net (code "51") (name "/SDA") (class "Default")
      (node (ref "J4") (pin "3") (pinfunction "3_3") (pintype "passive"))
      (node (ref "R35") (pin "1") (pinfunction "1_1") (pintype "passive"))
      (node (ref "U$1") (pin "GPIO4") (pinfunction "GPIO4_GPIO4") (pintype "bidirectional"))
    )
    (net (code "52") (name "/TX") (class "Default")
      (node (ref "JP2") (pin "2") (pinfunction "2_2") (pintype "passive"))
      (node (ref "U1") (pin "31") (pinfunction "PD1(TXD)_31") (pintype "bidirectional"))
    )
    (net (code "53") (name "/VBAT") (class "Default")
      (node (ref "D11") (pin "1") (pinfunction "+_1") (pintype "passive"))
      (node (ref "POWER") (pin "2") (pinfunction "KL_2") (pintype "passive"))
      (node (ref "R9") (pin "1") (pinfunction "1_1") (pintype "passive"))
    )
    (net (code "54") (name "/VOLTAGE+") (class "Default")
      (node (ref "P.S") (pin "1") (pinfunction "KL_1") (pintype "passive"))
      (node (ref "R39") (pin "1") (pinfunction "1_1") (pintype "passive"))
      (node (ref "R41") (pin "1") (pinfunction "1_1") (pintype "passive"))
    )
    (net (code "55") (name "Net-(D1-PadA)") (class "Default")
      (node (ref "D1") (pin "A") (pinfunction "A_A") (pintype "passive"))
      (node (ref "R23") (pin "2") (pinfunction "2_2") (pintype "passive"))
    )
    (net (code "56") (name "Net-(D2-PadA)") (class "Default")
      (node (ref "D2") (pin "A") (pinfunction "A_A") (pintype "passive"))
      (node (ref "R25") (pin "2") (pinfunction "2_2") (pintype "passive"))
    )
    (net (code "57") (name "Net-(D5--)") (class "Default")
      (node (ref "D5") (pin "2") (pinfunction "-_2") (pintype "passive"))
      (node (ref "OK14") (pin "4") (pinfunction "COL_4") (pintype "passive"))
      (node (ref "X2") (pin "5") (pinfunction "KL_5") (pintype "passive"))
    )
    (net (code "58") (name "Net-(D6--)") (class "Default")
      (node (ref "D6") (pin "2") (pinfunction "-_2") (pintype "passive"))
      (node (ref "OK1") (pin "4") (pinfunction "COL_4") (pintype "passive"))
      (node (ref "X2") (pin "4") (pinfunction "KL_4") (pintype "passive"))
    )
    (net (code "59") (name "Net-(D7--)") (class "Default")
      (node (ref "D7") (pin "2") (pinfunction "-_2") (pintype "passive"))
      (node (ref "OK2") (pin "4") (pinfunction "COL_4") (pintype "passive"))
      (node (ref "X2") (pin "3") (pinfunction "KL_3") (pintype "passive"))
    )
    (net (code "60") (name "Net-(D8--)") (class "Default")
      (node (ref "D8") (pin "2") (pinfunction "-_2") (pintype "passive"))
      (node (ref "OK4") (pin "4") (pinfunction "COL_4") (pintype "passive"))
      (node (ref "X2") (pin "2") (pinfunction "KL_2") (pintype "passive"))
    )
    (net (code "61") (name "Net-(D9--)") (class "Default")
      (node (ref "D9") (pin "2") (pinfunction "-_2") (pintype "passive"))
      (node (ref "OK3") (pin "4") (pinfunction "COL_4") (pintype "passive"))
      (node (ref "X2") (pin "1") (pinfunction "KL_1") (pintype "passive"))
    )
    (net (code "62") (name "Net-(IC2A-+IN)") (class "Default")
      (node (ref "IC2") (pin "3") (pinfunction "+IN_3") (pintype "input"))
      (node (ref "P.S") (pin "3") (pinfunction "KL_3") (pintype "passive"))
      (node (ref "R27") (pin "1") (pinfunction "1_1") (pintype "passive"))
    )
    (net (code "63") (name "Net-(IC2B-+IN)") (class "Default")
      (node (ref "IC2") (pin "5") (pinfunction "+IN_5") (pintype "input"))
      (node (ref "P.S") (pin "4") (pinfunction "KL_4") (pintype "passive"))
      (node (ref "R28") (pin "1") (pinfunction "1_1") (pintype "passive"))
    )
    (net (code "64") (name "Net-(IC3A-+IN)") (class "Default")
      (node (ref "C13") (pin "2") (pinfunction "2_2") (pintype "passive"))
      (node (ref "IC3") (pin "3") (pinfunction "+IN_3") (pintype "input"))
      (node (ref "L.S") (pin "2") (pinfunction "KL_2") (pintype "passive"))
      (node (ref "R29") (pin "1") (pinfunction "1_1") (pintype "passive"))
    )
    (net (code "65") (name "Net-(IC3B-+IN)") (class "Default")
      (node (ref "C12") (pin "2") (pinfunction "2_2") (pintype "passive"))
      (node (ref "IC3") (pin "5") (pinfunction "+IN_5") (pintype "input"))
      (node (ref "L.S") (pin "4") (pinfunction "KL_4") (pintype "passive"))
      (node (ref "R30") (pin "1") (pinfunction "1_1") (pintype "passive"))
    )
    (net (code "66") (name "Net-(IC6A-+IN)") (class "Default")
      (node (ref "IC6") (pin "3") (pinfunction "+IN_3") (pintype "input"))
      (node (ref "R21") (pin "1") (pinfunction "1_1") (pintype "passive"))
      (node (ref "R39") (pin "2") (pinfunction "2_2") (pintype "passive"))
    )
    (net (code "67") (name "Net-(IC6B-+IN)") (class "Default")
      (node (ref "IC6") (pin "5") (pinfunction "+IN_5") (pintype "input"))
      (node (ref "R41") (pin "2") (pinfunction "2_2") (pintype "passive"))
      (node (ref "R42") (pin "1") (pinfunction "1_1") (pintype "passive"))
    )
    (net (code "68") (name "Net-(IC6B--IN)") (class "Default")
      (node (ref "IC6") (pin "6") (pinfunction "-IN_6") (pintype "input"))
      (node (ref "R38") (pin "2") (pinfunction "2_2") (pintype "passive"))
      (node (ref "R40") (pin "1") (pinfunction "1_1") (pintype "passive"))
    )
    (net (code "69") (name "Net-(OK1-A)") (class "Default")
      (node (ref "OK1") (pin "1") (pinfunction "A_1") (pintype "passive"))
      (node (ref "R19") (pin "1") (pinfunction "1_1") (pintype "passive"))
    )
    (net (code "70") (name "Net-(OK2-A)") (class "Default")
      (node (ref "OK2") (pin "1") (pinfunction "A_1") (pintype "passive"))
      (node (ref "R20") (pin "1") (pinfunction "1_1") (pintype "passive"))
    )
    (net (code "71") (name "Net-(OK3-A)") (class "Default")
      (node (ref "OK3") (pin "1") (pinfunction "A_1") (pintype "passive"))
      (node (ref "R2") (pin "1") (pinfunction "1_1") (pintype "passive"))
    )
    (net (code "72") (name "Net-(OK4-A)") (class "Default")
      (node (ref "OK4") (pin "1") (pinfunction "A_1") (pintype "passive"))
      (node (ref "R37") (pin "1") (pinfunction "1_1") (pintype "passive"))
    )
    (net (code "73") (name "Net-(OK5-A)") (class "Default")
      (node (ref "OK5") (pin "1") (pinfunction "A_1") (pintype "passive"))
      (node (ref "R16") (pin "1") (pinfunction "1_1") (pintype "passive"))
    )
    (net (code "74") (name "Net-(OK5-A1)") (class "Default")
      (node (ref "OK5") (pin "4") (pinfunction "A1_4") (pintype "passive"))
      (node (ref "X1") (pin "2") (pinfunction "KL_2") (pintype "passive"))
    )
    (net (code "75") (name "Net-(OK6-A)") (class "Default")
      (node (ref "OK6") (pin "1") (pinfunction "A_1") (pintype "passive"))
      (node (ref "R17") (pin "1") (pinfunction "1_1") (pintype "passive"))
    )
    (net (code "76") (name "Net-(OK6-A1)") (class "Default")
      (node (ref "OK6") (pin "4") (pinfunction "A1_4") (pintype "passive"))
      (node (ref "X1") (pin "3") (pinfunction "KL_3") (pintype "passive"))
    )
    (net (code "77") (name "Net-(OK7-A)") (class "Default")
      (node (ref "OK7") (pin "1") (pinfunction "A_1") (pintype "passive"))
      (node (ref "R18") (pin "1") (pinfunction "1_1") (pintype "passive"))
    )
    (net (code "78") (name "Net-(OK7-A1)") (class "Default")
      (node (ref "OK7") (pin "4") (pinfunction "A1_4") (pintype "passive"))
      (node (ref "X1") (pin "4") (pinfunction "KL_4") (pintype "passive"))
    )
    (net (code "79") (name "Net-(OK13-A)") (class "Default")
      (node (ref "OK13") (pin "1") (pinfunction "A_1") (pintype "passive"))
      (node (ref "R31") (pin "1") (pinfunction "1_1") (pintype "passive"))
    )
    (net (code "80") (name "Net-(OK14-A)") (class "Default")
      (node (ref "OK14") (pin "1") (pinfunction "A_1") (pintype "passive"))
      (node (ref "R11") (pin "1") (pinfunction "1_1") (pintype "passive"))
    )
    (net (code "81") (name "Net-(OK15-A)") (class "Default")
      (node (ref "OK15") (pin "1") (pinfunction "A_1") (pintype "passive"))
      (node (ref "R32") (pin "2") (pinfunction "2_2") (pintype "passive"))
    )
    (net (code "82") (name "Net-(OK17-A)") (class "Default")
      (node (ref "OK17") (pin "1") (pinfunction "A_1") (pintype "passive"))
      (node (ref "R10") (pin "1") (pinfunction "1_1") (pintype "passive"))
    )
    (net (code "83") (name "Net-(OK18-A)") (class "Default")
      (node (ref "OK18") (pin "1") (pinfunction "A_1") (pintype "passive"))
      (node (ref "R14") (pin "1") (pinfunction "1_1") (pintype "passive"))
    )
    (net (code "84") (name "Net-(P.SB-KL)") (class "Default")
      (node (ref "P.S") (pin "2") (pinfunction "KL_2") (pintype "passive"))
      (node (ref "R38") (pin "1") (pinfunction "1_1") (pintype "passive"))
    )
    (net (code "85") (name "Net-(R8-Pad1)") (class "Default")
      (node (ref "R8") (pin "1") (pinfunction "1_1") (pintype "passive"))
      (node (ref "U$1") (pin "CH_PD") (pinfunction "CH_PD_CH_PD") (pintype "bidirectional"))
    )
    (net (code "86") (name "Net-(SWB-KL)") (class "Default")
      (node (ref "R10") (pin "2") (pinfunction "2_2") (pintype "passive"))
      (node (ref "SW") (pin "2") (pinfunction "KL_2") (pintype "passive"))
    )
    (net (code "87") (name "Net-(SWC-KL)") (class "Default")
      (node (ref "R14") (pin "2") (pinfunction "2_2") (pintype "passive"))
      (node (ref "SW") (pin "3") (pinfunction "KL_3") (pintype "passive"))
    )
    (net (code "88") (name "Net-(U$1-RESET)") (class "Default")
      (node (ref "R7") (pin "1") (pinfunction "1_1") (pintype "passive"))
      (node (ref "U$1") (pin "REST") (pinfunction "RESET_REST") (pintype "bidirectional"))
    )
    (net (code "89") (name "Net-(U1-AREF)") (class "Default")
      (node (ref "C2") (pin "+") (pinfunction "+_+") (pintype "passive"))
      (node (ref "U1") (pin "20") (pinfunction "AREF_20") (pintype "bidirectional"))
    )
    (net (code "90") (name "unconnected-(U$1-PadADC)") (class "Default")
      (node (ref "U$1") (pin "ADC") (pinfunction "ADC_ADC") (pintype "bidirectional"))
    )
    (net (code "91") (name "unconnected-(U1-PB6(XTAL1{slash}TOSC1)-Pad7)") (class "Default")
      (node (ref "U1") (pin "7") (pinfunction "PB6(XTAL1/TOSC1)_7") (pintype "bidirectional"))
    )
    (net (code "92") (name "unconnected-(U1-PB7(XTAL2{slash}TOSC2)-Pad8)") (class "Default")
      (node (ref "U1") (pin "8") (pinfunction "PB7(XTAL2/TOSC2)_8") (pintype "bidirectional"))
    )
  )
)
